# UART_Debug.net
KiCad netlist of a schematic drawn in Altium Designer
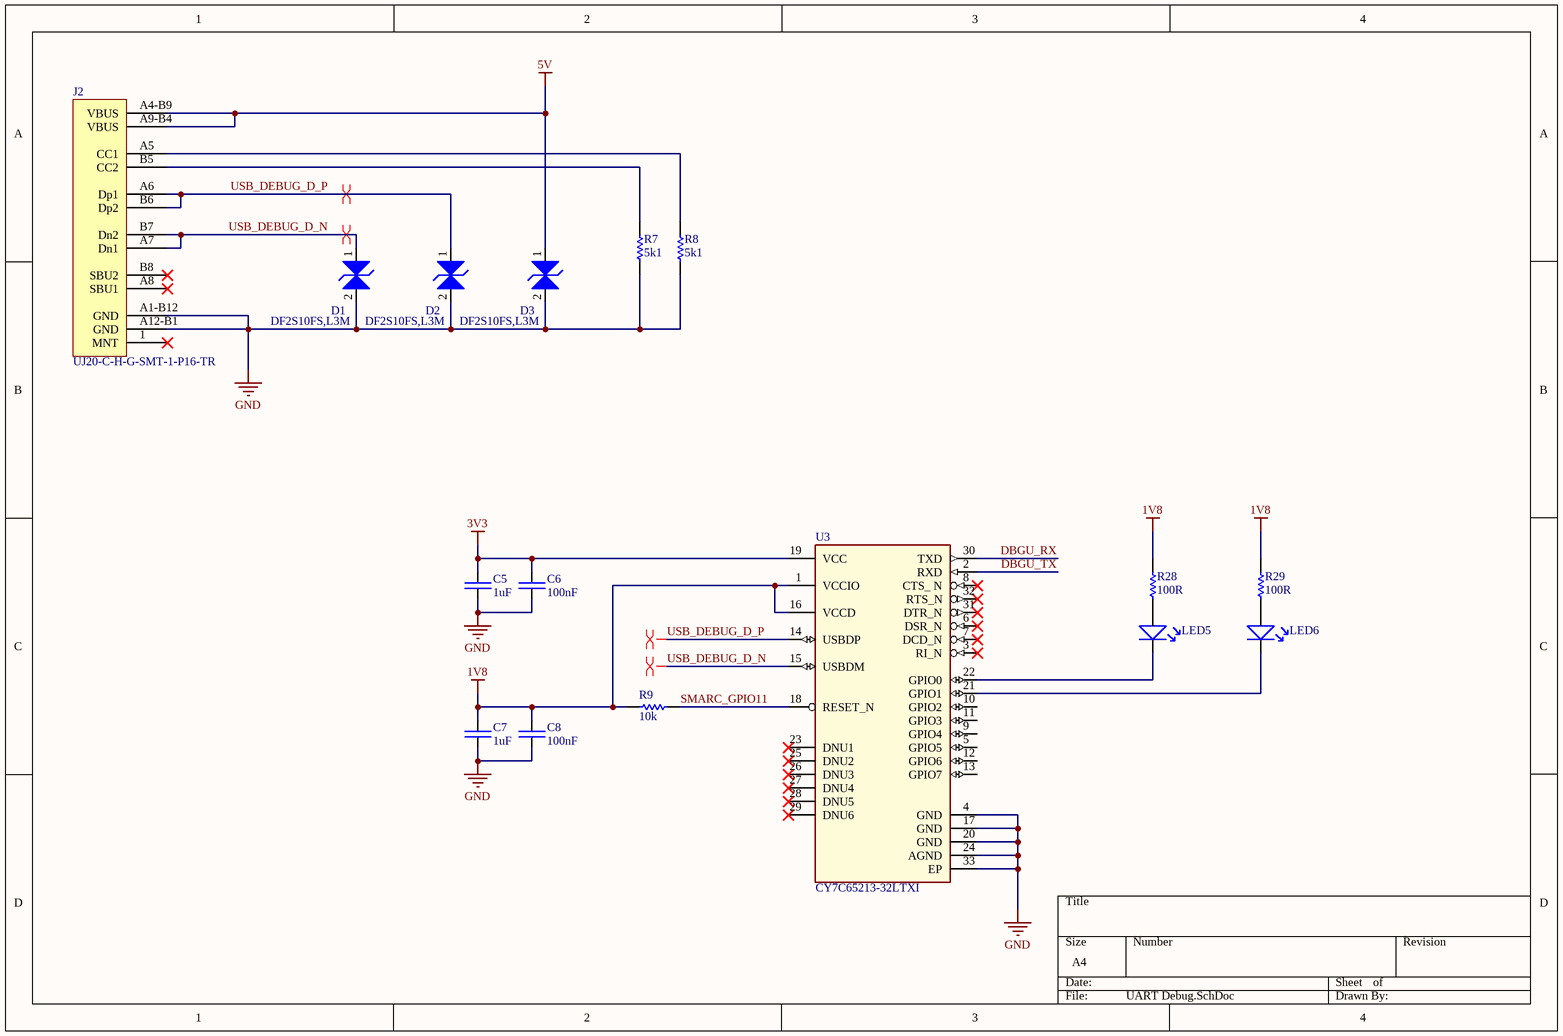
[diagram p0: UART Debug.SchDoc]

(export (version "E")
  (design (tool "Eeschema 10.0.6"))
  (components
    (comp (ref "C5")
      (value "1uF")
      (footprint "CAP-0805")
      (description "Capacitor chip unpolarized. 0805")
      (libsource (lib "Master") (part "CAP-0805"))
    )
    (comp (ref "C6")
      (value "100nF")
      (footprint "CAP-0603")
      (description "Capacitor chip unpolarized. 0603")
      (libsource (lib "Master") (part "CAP-0603"))
    )
    (comp (ref "C7")
      (value "1uF")
      (footprint "CAP-0805")
      (description "Capacitor chip unpolarized. 0805")
      (libsource (lib "Master") (part "CAP-0805"))
    )
    (comp (ref "C8")
      (value "100nF")
      (footprint "CAP-0603")
      (description "Capacitor chip unpolarized. 0603")
      (libsource (lib "Master") (part "CAP-0603"))
    )
    (comp (ref "D1")
      (value "DF2S10FS,L3M")
      (footprint "DF2S10FS,L3M")
      (description "TVS Diode 8VRM")
      (libsource (lib "Master") (part "DF2S10FS,L3M"))
    )
    (comp (ref "D2")
      (value "DF2S10FS,L3M")
      (footprint "DF2S10FS,L3M")
      (description "TVS Diode 8VRM")
      (libsource (lib "Master") (part "DF2S10FS,L3M"))
    )
    (comp (ref "D3")
      (value "DF2S10FS,L3M")
      (footprint "DF2S10FS,L3M")
      (description "TVS Diode 8VRM")
      (libsource (lib "Master") (part "DF2S10FS,L3M"))
    )
    (comp (ref "J2")
      (value "UJ20-C-H-G-SMT-1-P16-TR")
      (footprint "UJ20-C-H-G-SMT-1-P16-TR")
      (description "USB-C Conn Surface Mount (16 + 8 Dummy)")
      (libsource (lib "Master") (part "UJ20-C-H-G-SMT-1-P16-TR"))
    )
    (comp (ref "LED5") (value "0603 LED") (footprint "0603 LED") (libsource (lib "Master") (part "0603 LED")))
    (comp (ref "LED6") (value "0603 LED") (footprint "0603 LED") (libsource (lib "Master") (part "0603 LED")))
    (comp (ref "R7")
      (value "5k1")
      (footprint "RES-0603")
      (description "Resistor chip. 0603")
      (libsource (lib "Master") (part "RES-0603"))
    )
    (comp (ref "R8")
      (value "5k1")
      (footprint "RES-0603")
      (description "Resistor chip. 0603")
      (libsource (lib "Master") (part "RES-0603"))
    )
    (comp (ref "R9")
      (value "10k")
      (footprint "RES-0603")
      (description "Resistor chip. 0603")
      (libsource (lib "Master") (part "RES-0603"))
    )
    (comp (ref "R28")
      (value "100R")
      (footprint "RES-0603")
      (description "Resistor chip. 0603")
      (libsource (lib "Master") (part "RES-0603"))
    )
    (comp (ref "R29")
      (value "100R")
      (footprint "RES-0603")
      (description "Resistor chip. 0603")
      (libsource (lib "Master") (part "RES-0603"))
    )
    (comp (ref "U3")
      (value "CY7C65213-32LTXI")
      (footprint "CY7C65213-32LTXI")
      (description "USB-UART LP Bridge Controller")
      (fields (field (name "MANUFACTURER") "Infineon Technologies"))
      (libsource (lib "Master") (part "CY7C65213-32LTXI"))
    )
  )
  (nets
    (net (code "1") (name "/DBGU_RX") (class "Default")
      (node (ref "U3") (pin "30") (pinfunction "TXD_30") (pintype "output"))
    )
    (net (code "2") (name "/DBGU_TX") (class "Default")
      (node (ref "U3") (pin "2") (pinfunction "RXD_2") (pintype "input"))
    )
    (net (code "3") (name "/SMARC_GPIO11") (class "Default")
      (node (ref "R9") (pin "2") (pintype "passive"))
      (node (ref "U3") (pin "18") (pinfunction "RESET_N_18") (pintype "passive"))
    )
    (net (code "4") (name "/USB_DEBUG_D_N") (class "Default")
      (node (ref "D1") (pin "1") (pintype "passive"))
      (node (ref "J2") (pin "A7") (pinfunction "Dn1_A7") (pintype "passive"))
      (node (ref "J2") (pin "B7") (pinfunction "Dn2_B7") (pintype "passive"))
      (node (ref "U3") (pin "15") (pinfunction "USBDM_15") (pintype "bidirectional"))
    )
    (net (code "5") (name "/USB_DEBUG_D_P") (class "Default")
      (node (ref "D2") (pin "1") (pintype "passive"))
      (node (ref "J2") (pin "A6") (pinfunction "Dp1_A6") (pintype "passive"))
      (node (ref "J2") (pin "B6") (pinfunction "Dp2_B6") (pintype "passive"))
      (node (ref "U3") (pin "14") (pinfunction "USBDP_14") (pintype "bidirectional"))
    )
    (net (code "6") (name "1V8") (class "Default")
      (node (ref "C7") (pin "2") (pintype "passive"))
      (node (ref "C8") (pin "2") (pintype "passive"))
      (node (ref "R28") (pin "2") (pintype "passive"))
      (node (ref "R29") (pin "2") (pintype "passive"))
      (node (ref "R9") (pin "1") (pintype "passive"))
      (node (ref "U3") (pin "1") (pinfunction "VCCIO_1") (pintype "power_in"))
      (node (ref "U3") (pin "16") (pinfunction "VCCD_16") (pintype "power_in"))
    )
    (net (code "7") (name "3V3") (class "Default")
      (node (ref "C5") (pin "2") (pintype "passive"))
      (node (ref "C6") (pin "2") (pintype "passive"))
      (node (ref "U3") (pin "19") (pinfunction "VCC_19") (pintype "power_in"))
    )
    (net (code "8") (name "5V") (class "Default")
      (node (ref "D3") (pin "1") (pintype "passive"))
      (node (ref "J2") (pin "A4-B9") (pinfunction "VBUS_A4-B9") (pintype "passive"))
      (node (ref "J2") (pin "A9-B4") (pinfunction "VBUS_A9-B4") (pintype "passive"))
    )
    (net (code "9") (name "GND") (class "Default")
      (node (ref "C5") (pin "1") (pintype "passive"))
      (node (ref "C6") (pin "1") (pintype "passive"))
      (node (ref "C7") (pin "1") (pintype "passive"))
      (node (ref "C8") (pin "1") (pintype "passive"))
      (node (ref "D1") (pin "2") (pintype "passive"))
      (node (ref "D2") (pin "2") (pintype "passive"))
      (node (ref "D3") (pin "2") (pintype "passive"))
      (node (ref "J2") (pin "A1-B12") (pinfunction "GND_A1-B12") (pintype "passive"))
      (node (ref "J2") (pin "A12-B1") (pinfunction "GND_A12-B1") (pintype "passive"))
      (node (ref "R7") (pin "1") (pintype "passive"))
      (node (ref "R8") (pin "1") (pintype "passive"))
      (node (ref "U3") (pin "17") (pinfunction "GND_17") (pintype "power_in"))
      (node (ref "U3") (pin "20") (pinfunction "GND_20") (pintype "power_in"))
      (node (ref "U3") (pin "24") (pinfunction "AGND_24") (pintype "power_in"))
      (node (ref "U3") (pin "33") (pinfunction "EP_33") (pintype "power_in"))
      (node (ref "U3") (pin "4") (pinfunction "GND_4") (pintype "power_in"))
    )
    (net (code "10") (name "Net-(J2-CC1)") (class "Default")
      (node (ref "J2") (pin "A5") (pinfunction "CC1_A5") (pintype "passive"))
      (node (ref "R8") (pin "2") (pintype "passive"))
    )
    (net (code "11") (name "Net-(J2-CC2)") (class "Default")
      (node (ref "J2") (pin "B5") (pinfunction "CC2_B5") (pintype "passive"))
      (node (ref "R7") (pin "2") (pintype "passive"))
    )
    (net (code "12") (name "Net-(LED5-5)") (class "Default")
      (node (ref "LED5") (pin "2") (pinfunction "5_2") (pintype "passive"))
      (node (ref "U3") (pin "22") (pinfunction "GPIO0_22") (pintype "bidirectional"))
    )
    (net (code "13") (name "Net-(LED5-6)") (class "Default")
      (node (ref "LED5") (pin "1") (pinfunction "6_1") (pintype "passive"))
      (node (ref "R28") (pin "1") (pintype "passive"))
    )
    (net (code "14") (name "Net-(LED6-5)") (class "Default")
      (node (ref "LED6") (pin "2") (pinfunction "5_2") (pintype "passive"))
      (node (ref "U3") (pin "21") (pinfunction "GPIO1_21") (pintype "bidirectional"))
    )
    (net (code "15") (name "Net-(LED6-6)") (class "Default")
      (node (ref "LED6") (pin "1") (pinfunction "6_1") (pintype "passive"))
      (node (ref "R29") (pin "1") (pintype "passive"))
    )
    (net (code "16") (name "unconnected-(J2-MNT-Pad1)") (class "Default")
      (node (ref "J2") (pin "1") (pinfunction "MNT_1") (pintype "passive+no_connect"))
    )
    (net (code "17") (name "unconnected-(J2-SBU1-PadA8)") (class "Default")
      (node (ref "J2") (pin "A8") (pinfunction "SBU1_A8") (pintype "passive+no_connect"))
    )
    (net (code "18") (name "unconnected-(J2-SBU2-PadB8)") (class "Default")
      (node (ref "J2") (pin "B8") (pinfunction "SBU2_B8") (pintype "passive+no_connect"))
    )
    (net (code "19") (name "unconnected-(U3-CTS__N-Pad8)") (class "Default")
      (node (ref "U3") (pin "8") (pinfunction "CTS__N_8") (pintype "input+no_connect"))
    )
    (net (code "20") (name "unconnected-(U3-DCD_N-Pad7)") (class "Default")
      (node (ref "U3") (pin "7") (pinfunction "DCD_N_7") (pintype "input+no_connect"))
    )
    (net (code "21") (name "unconnected-(U3-DNU1-Pad23)") (class "Default")
      (node (ref "U3") (pin "23") (pinfunction "DNU1_23") (pintype "passive+no_connect"))
    )
    (net (code "22") (name "unconnected-(U3-DNU2-Pad25)") (class "Default")
      (node (ref "U3") (pin "25") (pinfunction "DNU2_25") (pintype "passive+no_connect"))
    )
    (net (code "23") (name "unconnected-(U3-DNU3-Pad26)") (class "Default")
      (node (ref "U3") (pin "26") (pinfunction "DNU3_26") (pintype "passive+no_connect"))
    )
    (net (code "24") (name "unconnected-(U3-DNU4-Pad27)") (class "Default")
      (node (ref "U3") (pin "27") (pinfunction "DNU4_27") (pintype "passive+no_connect"))
    )
    (net (code "25") (name "unconnected-(U3-DNU5-Pad28)") (class "Default")
      (node (ref "U3") (pin "28") (pinfunction "DNU5_28") (pintype "passive+no_connect"))
    )
    (net (code "26") (name "unconnected-(U3-DNU6-Pad29)") (class "Default")
      (node (ref "U3") (pin "29") (pinfunction "DNU6_29") (pintype "passive+no_connect"))
    )
    (net (code "27") (name "unconnected-(U3-DSR_N-Pad6)") (class "Default")
      (node (ref "U3") (pin "6") (pinfunction "DSR_N_6") (pintype "input+no_connect"))
    )
    (net (code "28") (name "unconnected-(U3-DTR_N-Pad31)") (class "Default")
      (node (ref "U3") (pin "31") (pinfunction "DTR_N_31") (pintype "output+no_connect"))
    )
    (net (code "29") (name "unconnected-(U3-GPIO2-Pad10)") (class "Default")
      (node (ref "U3") (pin "10") (pinfunction "GPIO2_10") (pintype "bidirectional"))
    )
    (net (code "30") (name "unconnected-(U3-GPIO3-Pad11)") (class "Default")
      (node (ref "U3") (pin "11") (pinfunction "GPIO3_11") (pintype "bidirectional"))
    )
    (net (code "31") (name "unconnected-(U3-GPIO4-Pad9)") (class "Default")
      (node (ref "U3") (pin "9") (pinfunction "GPIO4_9") (pintype "bidirectional"))
    )
    (net (code "32") (name "unconnected-(U3-GPIO5-Pad5)") (class "Default")
      (node (ref "U3") (pin "5") (pinfunction "GPIO5_5") (pintype "bidirectional"))
    )
    (net (code "33") (name "unconnected-(U3-GPIO6-Pad12)") (class "Default")
      (node (ref "U3") (pin "12") (pinfunction "GPIO6_12") (pintype "bidirectional"))
    )
    (net (code "34") (name "unconnected-(U3-GPIO7-Pad13)") (class "Default")
      (node (ref "U3") (pin "13") (pinfunction "GPIO7_13") (pintype "bidirectional"))
    )
    (net (code "35") (name "unconnected-(U3-RI_N-Pad3)") (class "Default")
      (node (ref "U3") (pin "3") (pinfunction "RI_N_3") (pintype "input+no_connect"))
    )
    (net (code "36") (name "unconnected-(U3-RTS_N-Pad32)") (class "Default")
      (node (ref "U3") (pin "32") (pinfunction "RTS_N_32") (pintype "output+no_connect"))
    )
  )
)
